# aux.net
KiCad netlist of a schematic drawn in EAGLE
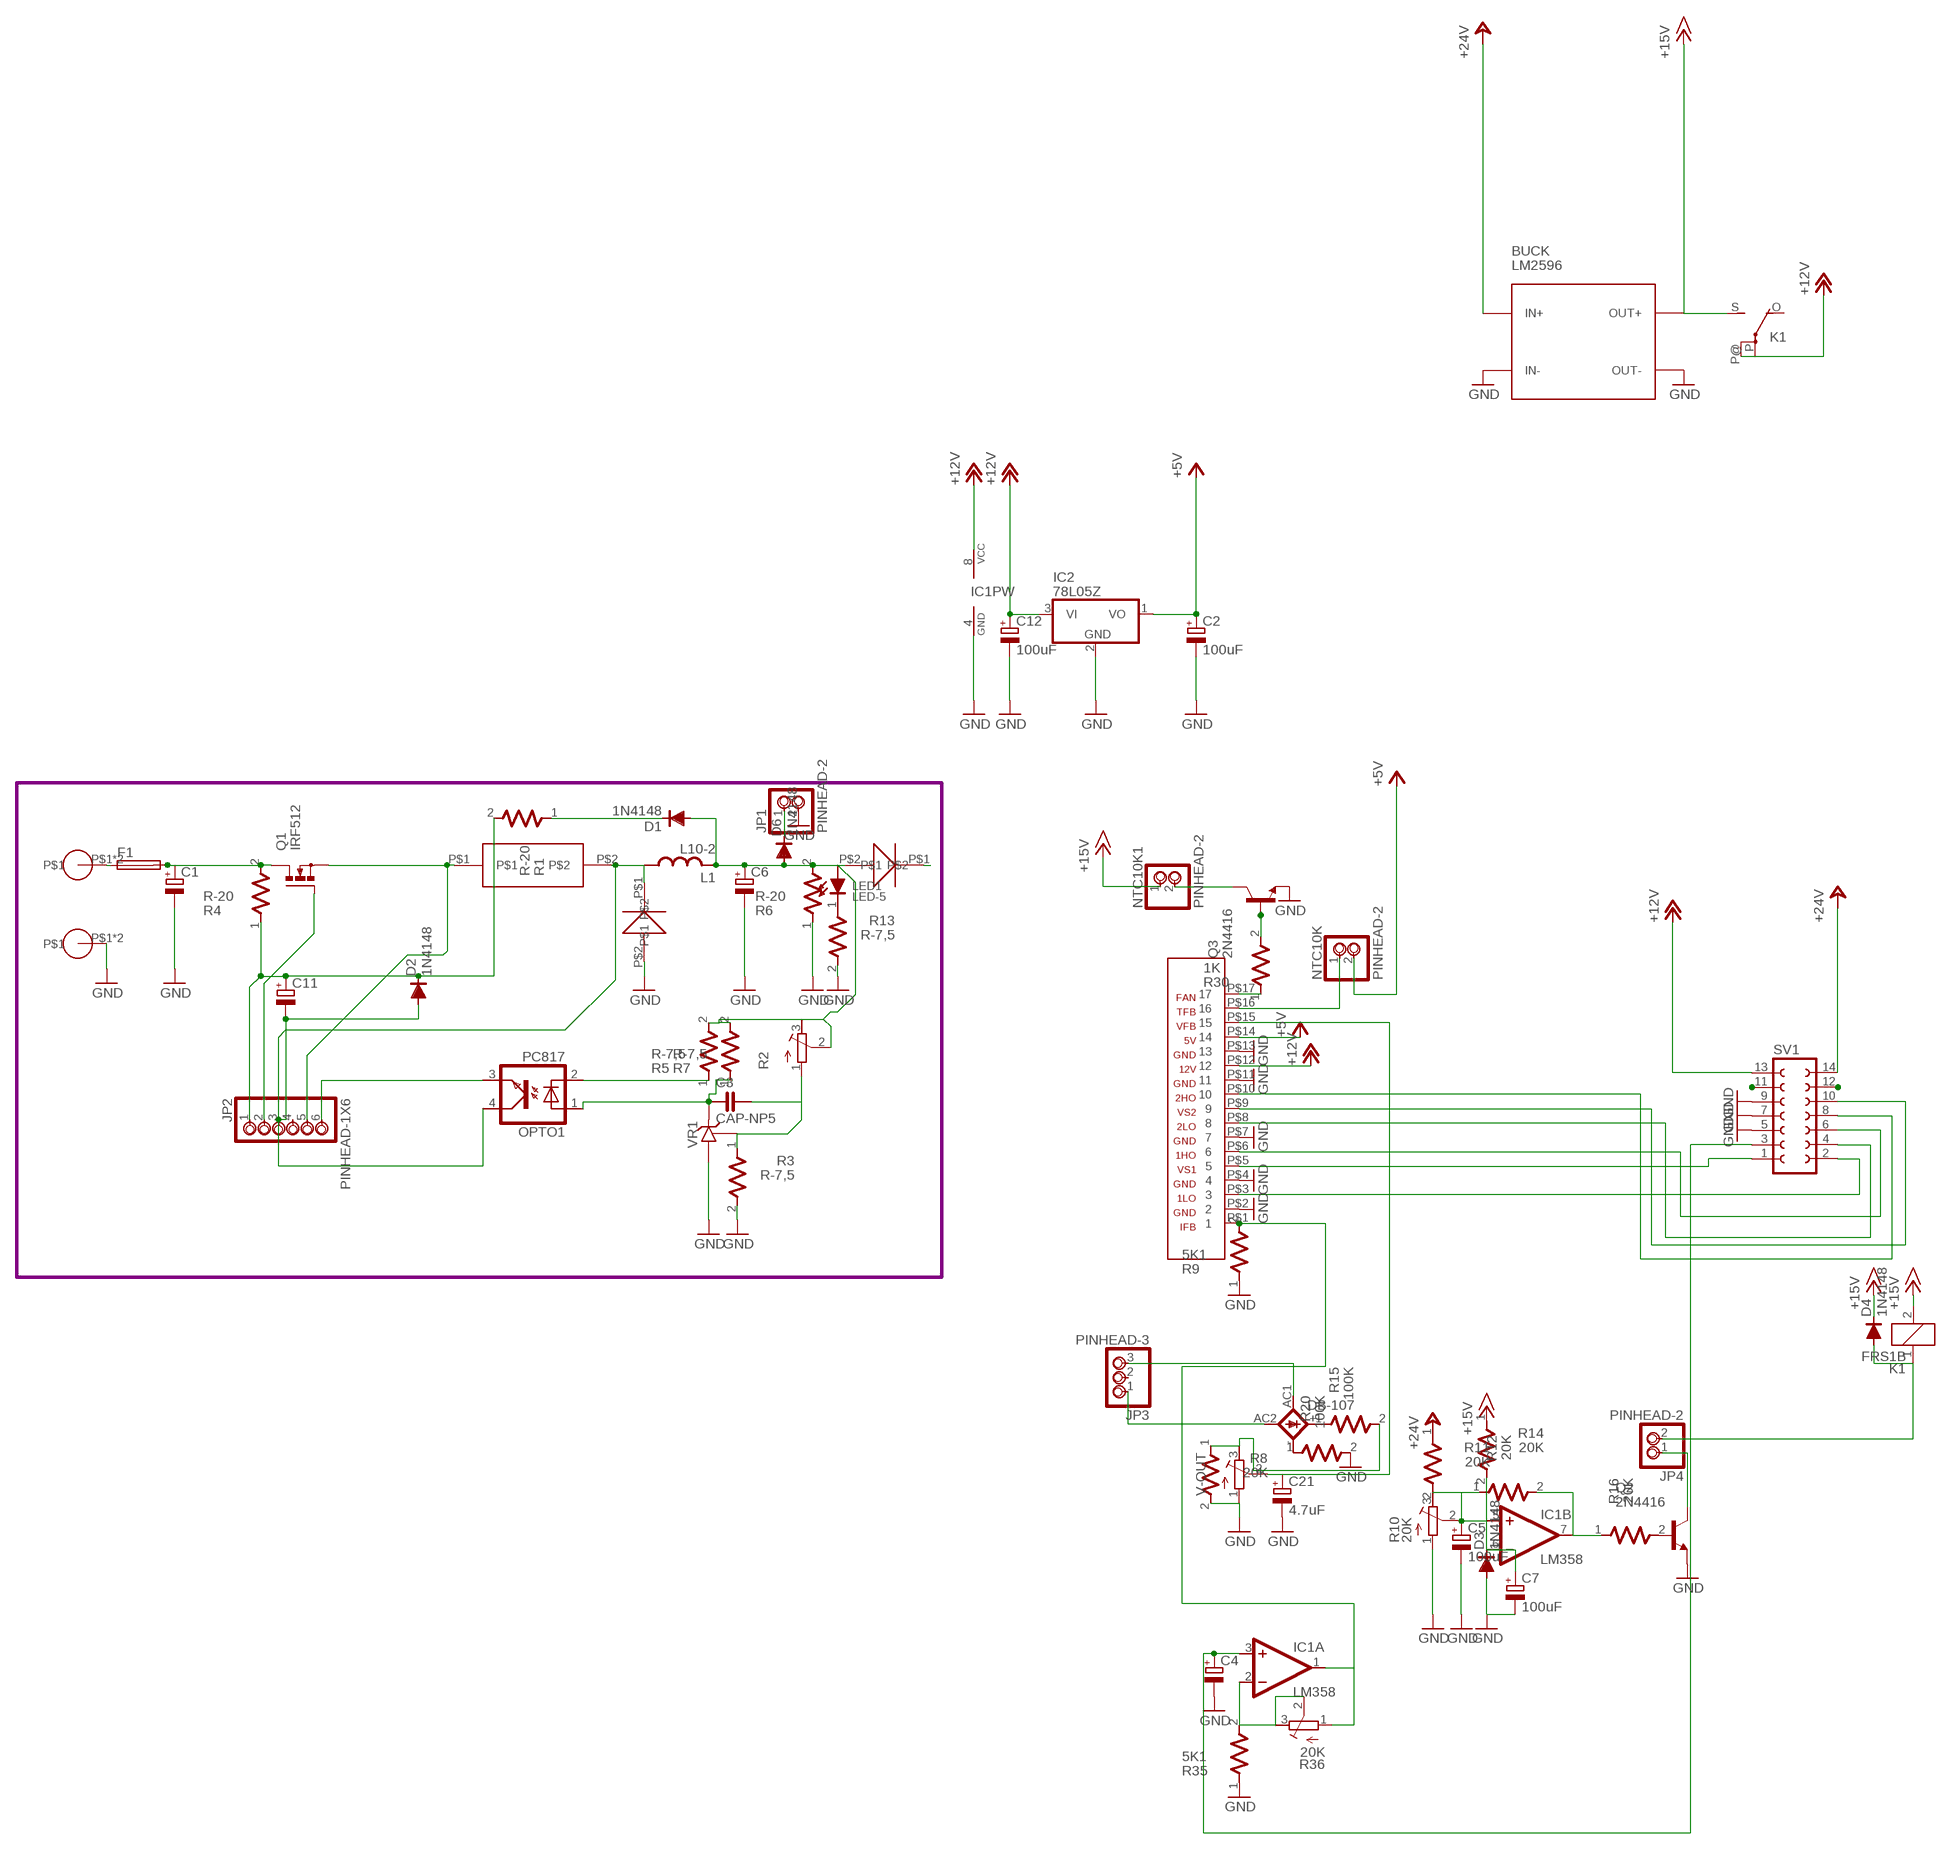
[diagram p0: schematic, sheet 1]

(export (version "E")
  (design (tool "Eeschema 10.0.6"))
  (components
    (comp (ref "BUCK")
      (value "LM2596")
      (footprint "eagle-import:DC-DC-STEP-DOWN-LM2596")
      (libsource (lib "eagle-import") (part "DC-DC-STEP-DOWN-LM2596"))
    )
    (comp (ref "C1")
      (value "CPOL-EUE7.5-18")
      (footprint "eagle-import:E7,5-18")
      (libsource (lib "eagle-import") (part "CPOL-EUE7.5-18"))
    )
    (comp (ref "C2")
      (value "100uF")
      (footprint "eagle-import:E2,5-7")
      (libsource (lib "eagle-import") (part "CPOL-EUE2.5-7"))
    )
    (comp (ref "C3")
      (value "CAP-NP5")
      (footprint "eagle-import:CAP-NP5")
      (libsource (lib "eagle-import") (part "CAP-NP5"))
    )
    (comp (ref "C4")
      (value "CPOL-EUE2.5-7")
      (footprint "eagle-import:E2,5-7")
      (libsource (lib "eagle-import") (part "CPOL-EUE2.5-7"))
    )
    (comp (ref "C5")
      (value "100uF")
      (footprint "eagle-import:E2,5-7")
      (libsource (lib "eagle-import") (part "CPOL-EUE2.5-7"))
    )
    (comp (ref "C6")
      (value "CPOL-EUE7.5-18")
      (footprint "eagle-import:E7,5-18")
      (libsource (lib "eagle-import") (part "CPOL-EUE7.5-18"))
    )
    (comp (ref "C7")
      (value "100uF")
      (footprint "eagle-import:E2,5-7")
      (libsource (lib "eagle-import") (part "CPOL-EUE2.5-7"))
    )
    (comp (ref "C11")
      (value "CPOL-EUE5-8.5")
      (footprint "eagle-import:E5-8,5")
      (libsource (lib "eagle-import") (part "CPOL-EUE5-8.5"))
    )
    (comp (ref "C12")
      (value "100uF")
      (footprint "eagle-import:E2,5-7")
      (libsource (lib "eagle-import") (part "CPOL-EUE2.5-7"))
    )
    (comp (ref "C21")
      (value "4.7uF")
      (footprint "eagle-import:E2,5-7")
      (libsource (lib "eagle-import") (part "CPOL-EUE2.5-7"))
    )
    (comp (ref "D1")
      (value "1N4148")
      (footprint "eagle-import:D-7,5")
      (libsource (lib "eagle-import") (part "1N4148"))
    )
    (comp (ref "D2")
      (value "1N4148")
      (footprint "eagle-import:D-7,5")
      (libsource (lib "eagle-import") (part "1N4148"))
    )
    (comp (ref "D3")
      (value "1N4148")
      (footprint "eagle-import:D-7,5")
      (libsource (lib "eagle-import") (part "1N4148"))
    )
    (comp (ref "D4")
      (value "1N4148")
      (footprint "eagle-import:D-7,5")
      (libsource (lib "eagle-import") (part "1N4148"))
    )
    (comp (ref "D6")
      (value "1N4148")
      (footprint "eagle-import:D-7,5")
      (libsource (lib "eagle-import") (part "1N4148"))
    )
    (comp (ref "DB-107")
      (value "CAU-1A")
      (footprint "eagle-import:CAU-1A")
      (libsource (lib "eagle-import") (part "CAU-1A"))
    )
    (comp (ref "F1")
      (value "SH22")
      (footprint "eagle-import:SH22")
      (libsource (lib "eagle-import") (part "SH22"))
    )
    (comp (ref "IC1")
      (value "LM358")
      (footprint "eagle-import:DIL-8")
      (libsource (lib "eagle-import") (part "LM358"))
    )
    (comp (ref "IC2")
      (value "78L05Z")
      (footprint "eagle-import:TO92")
      (libsource (lib "eagle-import") (part "78ZL05"))
    )
    (comp (ref "JP1")
      (value "PINHEAD-2")
      (footprint "eagle-import:PINHEAD-2")
      (libsource (lib "eagle-import") (part "chuong_PINHEAD-2"))
    )
    (comp (ref "JP2")
      (value "PINHEAD-1X6")
      (footprint "eagle-import:PINHEAD-1X6")
      (libsource (lib "eagle-import") (part "PINHEAD-1X6"))
    )
    (comp (ref "JP3")
      (value "PINHEAD-3")
      (footprint "eagle-import:PINHEAD-3")
      (libsource (lib "eagle-import") (part "PINHEAD-3"))
    )
    (comp (ref "JP4")
      (value "PINHEAD-2")
      (footprint "eagle-import:PINHEAD-2")
      (libsource (lib "eagle-import") (part "chuong_PINHEAD-2"))
    )
    (comp (ref "K1")
      (value "FRS1B")
      (footprint "eagle-import:FRS1B")
      (libsource (lib "eagle-import") (part "FRS1B"))
    )
    (comp (ref "L1")
      (value "L10-2")
      (footprint "eagle-import:L10-2")
      (libsource (lib "eagle-import") (part "L10-2"))
    )
    (comp (ref "LED1")
      (value "LED-5")
      (footprint "eagle-import:LED5")
      (libsource (lib "eagle-import") (part "LED-5"))
    )
    (comp (ref "NTC10K")
      (value "PINHEAD-2")
      (footprint "eagle-import:PINHEAD-2")
      (libsource (lib "eagle-import") (part "PINHEAD-2"))
    )
    (comp (ref "NTC10K1")
      (value "PINHEAD-2")
      (footprint "eagle-import:PINHEAD-2")
      (libsource (lib "eagle-import") (part "PINHEAD-2"))
    )
    (comp (ref "OPTO1")
      (value "PC817")
      (footprint "eagle-import:DIL-04")
      (libsource (lib "eagle-import") (part "PC817"))
    )
    (comp (ref "Q1")
      (value "IRF512")
      (footprint "eagle-import:TO220BV")
      (libsource (lib "eagle-import") (part "IRF512"))
    )
    (comp (ref "Q2")
      (value "2N4416")
      (footprint "eagle-import:TO92")
      (libsource (lib "eagle-import") (part "2N4416"))
    )
    (comp (ref "Q3")
      (value "2N4416")
      (footprint "eagle-import:TO92")
      (libsource (lib "eagle-import") (part "2N4416"))
    )
    (comp (ref "R1")
      (value "R-20")
      (footprint "eagle-import:R-20")
      (libsource (lib "eagle-import") (part "R-20"))
    )
    (comp (ref "R2")
      (value "R-TRIMM64W")
      (footprint "eagle-import:RTRIM64W")
      (libsource (lib "eagle-import") (part "R-TRIMM64W"))
    )
    (comp (ref "R3")
      (value "R-7,5")
      (footprint "eagle-import:R-7,5")
      (libsource (lib "eagle-import") (part "R-7,5"))
    )
    (comp (ref "R4")
      (value "R-20")
      (footprint "eagle-import:R-20")
      (libsource (lib "eagle-import") (part "R-20"))
    )
    (comp (ref "R5")
      (value "R-7,5")
      (footprint "eagle-import:R-7,5")
      (libsource (lib "eagle-import") (part "R-7,5"))
    )
    (comp (ref "R6")
      (value "R-20")
      (footprint "eagle-import:R-20")
      (libsource (lib "eagle-import") (part "R-20"))
    )
    (comp (ref "R7")
      (value "R-7,5")
      (footprint "eagle-import:R-7,5")
      (libsource (lib "eagle-import") (part "R-7,5"))
    )
    (comp (ref "R8")
      (value "20K")
      (footprint "eagle-import:R-7,5")
      (libsource (lib "eagle-import") (part "R-7,5"))
    )
    (comp (ref "R9")
      (value "5K1")
      (footprint "eagle-import:R-7,5")
      (libsource (lib "eagle-import") (part "R-7,5"))
    )
    (comp (ref "R10")
      (value "20K")
      (footprint "eagle-import:RTRIM64W")
      (libsource (lib "eagle-import") (part "R-TRIMM64W"))
    )
    (comp (ref "R11")
      (value "20K")
      (footprint "eagle-import:R-7,5")
      (libsource (lib "eagle-import") (part "R-7,5"))
    )
    (comp (ref "R12")
      (value "20K")
      (footprint "eagle-import:R-7,5")
      (libsource (lib "eagle-import") (part "R-7,5"))
    )
    (comp (ref "R13")
      (value "R-7,5")
      (footprint "eagle-import:R-7,5")
      (libsource (lib "eagle-import") (part "R-7,5"))
    )
    (comp (ref "R14")
      (value "20K")
      (footprint "eagle-import:R-7,5")
      (libsource (lib "eagle-import") (part "R-7,5"))
    )
    (comp (ref "R15")
      (value "100K")
      (footprint "eagle-import:R-7,5")
      (libsource (lib "eagle-import") (part "R-7,5"))
    )
    (comp (ref "R16")
      (value "20K")
      (footprint "eagle-import:R-7,5")
      (libsource (lib "eagle-import") (part "R-7,5"))
    )
    (comp (ref "R20")
      (value "100K")
      (footprint "eagle-import:R-7,5")
      (libsource (lib "eagle-import") (part "R-7,5"))
    )
    (comp (ref "R30")
      (value "1K")
      (footprint "eagle-import:R-7,5")
      (libsource (lib "eagle-import") (part "R-7,5"))
    )
    (comp (ref "R35")
      (value "5K1")
      (footprint "eagle-import:R-7,5")
      (libsource (lib "eagle-import") (part "R-7,5"))
    )
    (comp (ref "R36")
      (value "20K")
      (footprint "eagle-import:RTRIM64W")
      (libsource (lib "eagle-import") (part "R-TRIMM64W"))
    )
    (comp (ref "SV1")
      (value "FE07-2")
      (footprint "eagle-import:FE07-2")
      (libsource (lib "eagle-import") (part "FE07-2"))
    )
    (comp (ref "U$1")
      (value "DSEI6060A")
      (footprint "eagle-import:DSEI6060A")
      (libsource (lib "eagle-import") (part "DSEI6060A"))
    )
    (comp (ref "U$2")
      (value "DSEI6060A")
      (footprint "eagle-import:DSEI6060A")
      (libsource (lib "eagle-import") (part "DSEI6060A"))
    )
    (comp (ref "U$3")
      (value "PIN5MM")
      (footprint "eagle-import:PIN5MM")
      (libsource (lib "eagle-import") (part "PIN5MM"))
    )
    (comp (ref "U$4")
      (value "PIN5MM")
      (footprint "eagle-import:PIN5MM")
      (libsource (lib "eagle-import") (part "PIN5MM"))
    )
    (comp (ref "U$5")
      (value "SHUNT-0.01R")
      (footprint "eagle-import:SHUNT-0.01R")
      (libsource (lib "eagle-import") (part "SHUNT-0.01R"))
    )
    (comp (ref "U$11")
      (value "EGS002")
      (footprint "eagle-import:EGS002")
      (libsource (lib "eagle-import") (part "EGS002"))
    )
    (comp (ref "V-OUT")
      (value "R-TRIMM64W")
      (footprint "eagle-import:RTRIM64W")
      (libsource (lib "eagle-import") (part "R-TRIMM64W"))
    )
    (comp (ref "VR1")
      (value "TL431CLP")
      (footprint "eagle-import:TO92-CLP")
      (libsource (lib "eagle-import") (part "TL431CLP"))
    )
  )
  (nets
    (net (code "1") (name "+5V") (class "Default")
      (node (ref "C2") (pin "+") (pinfunction "+_+") (pintype "passive"))
      (node (ref "IC2") (pin "1") (pinfunction "VO_1") (pintype "passive"))
      (node (ref "NTC10K") (pin "2") (pinfunction "2_2") (pintype "passive"))
      (node (ref "U$11") (pin "P$14") (pinfunction "14_P$14") (pintype "bidirectional"))
    )
    (net (code "2") (name "+12V") (class "Default")
      (node (ref "C12") (pin "+") (pinfunction "+_+") (pintype "passive"))
      (node (ref "IC1") (pin "8") (pinfunction "VCC_8") (pintype "power_in"))
      (node (ref "IC2") (pin "3") (pinfunction "VI_3") (pintype "input"))
      (node (ref "K1") (pin "P") (pinfunction "P_P") (pintype "passive"))
      (node (ref "K1") (pin "P@") (pinfunction "P_P@") (pintype "passive"))
      (node (ref "SV1") (pin "13") (pinfunction "13_13") (pintype "passive"))
      (node (ref "U$11") (pin "P$12") (pinfunction "12_P$12") (pintype "bidirectional"))
    )
    (net (code "3") (name "+15V") (class "Default")
      (node (ref "BUCK") (pin "OUT+") (pinfunction "OUT+_OUT+") (pintype "bidirectional"))
      (node (ref "D4") (pin "C") (pinfunction "C_C") (pintype "passive"))
      (node (ref "K1") (pin "2") (pinfunction "2_2") (pintype "passive"))
      (node (ref "K1") (pin "S") (pinfunction "S_S") (pintype "passive"))
      (node (ref "NTC10K1") (pin "1") (pinfunction "1_1") (pintype "passive"))
      (node (ref "R14") (pin "1") (pinfunction "1_1") (pintype "passive"))
    )
    (net (code "4") (name "+24V") (class "Default")
      (node (ref "BUCK") (pin "IN+") (pinfunction "IN+_IN+") (pintype "bidirectional"))
      (node (ref "R11") (pin "1") (pinfunction "1_1") (pintype "passive"))
      (node (ref "SV1") (pin "14") (pinfunction "14_14") (pintype "passive"))
    )
    (net (code "5") (name "GND") (class "Default")
      (node (ref "BUCK") (pin "IN-") (pinfunction "IN-_IN-") (pintype "bidirectional"))
      (node (ref "BUCK") (pin "OUT-") (pinfunction "OUT-_OUT-") (pintype "bidirectional"))
      (node (ref "C1") (pin "-") (pinfunction "-_-") (pintype "passive"))
      (node (ref "C12") (pin "-") (pinfunction "-_-") (pintype "passive"))
      (node (ref "C2") (pin "-") (pinfunction "-_-") (pintype "passive"))
      (node (ref "C21") (pin "-") (pinfunction "-_-") (pintype "passive"))
      (node (ref "C4") (pin "-") (pinfunction "-_-") (pintype "passive"))
      (node (ref "C5") (pin "-") (pinfunction "-_-") (pintype "passive"))
      (node (ref "C6") (pin "-") (pinfunction "-_-") (pintype "passive"))
      (node (ref "C7") (pin "-") (pinfunction "-_-") (pintype "passive"))
      (node (ref "D3") (pin "A") (pinfunction "A_A") (pintype "passive"))
      (node (ref "IC1") (pin "4") (pinfunction "GND_4") (pintype "power_in"))
      (node (ref "IC2") (pin "2") (pinfunction "GND_2") (pintype "passive"))
      (node (ref "JP1") (pin "2") (pinfunction "2_2") (pintype "passive"))
      (node (ref "Q2") (pin "3") (pinfunction "E_3") (pintype "passive"))
      (node (ref "Q3") (pin "3") (pinfunction "E_3") (pintype "passive"))
      (node (ref "R10") (pin "1") (pinfunction "A_1") (pintype "passive"))
      (node (ref "R13") (pin "2") (pinfunction "2_2") (pintype "passive"))
      (node (ref "R20") (pin "2") (pinfunction "2_2") (pintype "passive"))
      (node (ref "R3") (pin "2") (pinfunction "2_2") (pintype "passive"))
      (node (ref "R35") (pin "1") (pinfunction "1_1") (pintype "passive"))
      (node (ref "R6") (pin "1") (pinfunction "1_1") (pintype "passive"))
      (node (ref "R8") (pin "2") (pinfunction "2_2") (pintype "passive"))
      (node (ref "R9") (pin "1") (pinfunction "1_1") (pintype "passive"))
      (node (ref "SV1") (pin "5") (pinfunction "5_5") (pintype "passive"))
      (node (ref "SV1") (pin "7") (pinfunction "7_7") (pintype "passive"))
      (node (ref "SV1") (pin "9") (pinfunction "9_9") (pintype "passive"))
      (node (ref "U$1") (pin "P$2") (pinfunction "P$2_P$2") (pintype "bidirectional"))
      (node (ref "U$11") (pin "P$11") (pinfunction "11_P$11") (pintype "bidirectional"))
      (node (ref "U$11") (pin "P$13") (pinfunction "13_P$13") (pintype "bidirectional"))
      (node (ref "U$11") (pin "P$2") (pinfunction "2_P$2") (pintype "bidirectional"))
      (node (ref "U$11") (pin "P$4") (pinfunction "4_P$4") (pintype "bidirectional"))
      (node (ref "U$11") (pin "P$7") (pinfunction "7_P$7") (pintype "bidirectional"))
      (node (ref "U$3") (pin "P$1") (pinfunction "P$1_P$1") (pintype "bidirectional"))
      (node (ref "U$3") (pin "P$2") (pinfunction "P$1_P$2") (pintype "bidirectional"))
      (node (ref "V-OUT") (pin "1") (pinfunction "A_1") (pintype "passive"))
      (node (ref "VR1") (pin "A") (pinfunction "A_A") (pintype "passive"))
    )
    (net (code "6") (name "Net-(D1-PadC)") (class "Default")
      (node (ref "D1") (pin "C") (pinfunction "C_C") (pintype "passive"))
      (node (ref "R1") (pin "1") (pinfunction "1_1") (pintype "passive"))
    )
    (net (code "7") (name "Net-(D4-PadA)") (class "Default")
      (node (ref "D4") (pin "A") (pinfunction "A_A") (pintype "passive"))
      (node (ref "JP4") (pin "2") (pinfunction "2_2") (pintype "passive"))
      (node (ref "K1") (pin "1") (pinfunction "1_1") (pintype "passive"))
    )
    (net (code "8") (name "Net-(D6-PadC)") (class "Default")
      (node (ref "D6") (pin "C") (pinfunction "C_C") (pintype "passive"))
      (node (ref "JP1") (pin "1") (pinfunction "1_1") (pintype "passive"))
    )
    (net (code "9") (name "Net-(DB-107--)") (class "Default")
      (node (ref "DB-107") (pin "AC2") (pinfunction "-_AC2") (pintype "passive"))
      (node (ref "JP3") (pin "1") (pinfunction "1_1") (pintype "passive"))
    )
    (net (code "10") (name "Net-(DB-107-AC2)") (class "Default")
      (node (ref "DB-107") (pin "-") (pinfunction "AC2_-") (pintype "passive"))
      (node (ref "R20") (pin "1") (pinfunction "1_1") (pintype "passive"))
    )
    (net (code "11") (name "Net-(DB-107-Pad+)") (class "Default")
      (node (ref "DB-107") (pin "+") (pinfunction "+_+") (pintype "passive"))
      (node (ref "R15") (pin "1") (pinfunction "1_1") (pintype "passive"))
    )
    (net (code "12") (name "Net-(DB-107-PadAC1)") (class "Default")
      (node (ref "DB-107") (pin "AC1") (pinfunction "AC1_AC1") (pintype "passive"))
      (node (ref "JP3") (pin "3") (pinfunction "3_3") (pintype "passive"))
    )
    (net (code "13") (name "Net-(F1-Pad1)") (class "Default")
      (node (ref "F1") (pin "1") (pinfunction "1_1") (pintype "passive"))
      (node (ref "U$4") (pin "P$1") (pinfunction "P$1_P$1") (pintype "bidirectional"))
      (node (ref "U$4") (pin "P$2") (pinfunction "P$1_P$2") (pintype "bidirectional"))
    )
    (net (code "14") (name "Net-(IC1A-+IN)") (class "Default")
      (node (ref "C4") (pin "+") (pinfunction "+_+") (pintype "passive"))
      (node (ref "IC1") (pin "3") (pinfunction "+IN_3") (pintype "input"))
      (node (ref "SV1") (pin "3") (pinfunction "3_3") (pintype "passive"))
    )
    (net (code "15") (name "Net-(IC1A--IN)") (class "Default")
      (node (ref "IC1") (pin "2") (pinfunction "-IN_2") (pintype "input"))
      (node (ref "R35") (pin "2") (pinfunction "2_2") (pintype "passive"))
      (node (ref "R36") (pin "2") (pinfunction "S_2") (pintype "passive"))
      (node (ref "R36") (pin "3") (pinfunction "E_3") (pintype "passive"))
    )
    (net (code "16") (name "Net-(IC1A-OUT)") (class "Default")
      (node (ref "IC1") (pin "1") (pinfunction "OUT_1") (pintype "output"))
      (node (ref "R36") (pin "1") (pinfunction "A_1") (pintype "passive"))
      (node (ref "R9") (pin "2") (pinfunction "2_2") (pintype "passive"))
      (node (ref "U$11") (pin "P$1") (pinfunction "1_P$1") (pintype "bidirectional"))
    )
    (net (code "17") (name "Net-(IC1B-+IN)") (class "Default")
      (node (ref "C5") (pin "+") (pinfunction "+_+") (pintype "passive"))
      (node (ref "IC1") (pin "5") (pinfunction "+IN_5") (pintype "input"))
      (node (ref "R10") (pin "2") (pinfunction "S_2") (pintype "passive"))
      (node (ref "R10") (pin "3") (pinfunction "E_3") (pintype "passive"))
      (node (ref "R11") (pin "2") (pinfunction "2_2") (pintype "passive"))
      (node (ref "R12") (pin "1") (pinfunction "1_1") (pintype "passive"))
    )
    (net (code "18") (name "Net-(IC1B--IN)") (class "Default")
      (node (ref "C7") (pin "+") (pinfunction "+_+") (pintype "passive"))
      (node (ref "D3") (pin "C") (pinfunction "C_C") (pintype "passive"))
      (node (ref "IC1") (pin "6") (pinfunction "-IN_6") (pintype "input"))
      (node (ref "R14") (pin "2") (pinfunction "2_2") (pintype "passive"))
    )
    (net (code "19") (name "Net-(IC1B-OUT)") (class "Default")
      (node (ref "IC1") (pin "7") (pinfunction "OUT_7") (pintype "output"))
      (node (ref "R12") (pin "2") (pinfunction "2_2") (pintype "passive"))
      (node (ref "R16") (pin "1") (pinfunction "1_1") (pintype "passive"))
    )
    (net (code "20") (name "Net-(JP2-Pad2)") (class "Default")
      (node (ref "JP2") (pin "2") (pinfunction "2_2") (pintype "passive"))
      (node (ref "Q1") (pin "G") (pinfunction "G_G") (pintype "passive"))
    )
    (net (code "21") (name "Net-(JP2-Pad5)") (class "Default")
      (node (ref "JP2") (pin "5") (pinfunction "5_5") (pintype "passive"))
      (node (ref "Q1") (pin "S") (pinfunction "S_S") (pintype "passive"))
      (node (ref "U$5") (pin "P$1") (pinfunction "P$1_P$1") (pintype "bidirectional"))
    )
    (net (code "22") (name "Net-(LED1-PadK)") (class "Default")
      (node (ref "LED1") (pin "K") (pinfunction "K_K") (pintype "passive"))
      (node (ref "R13") (pin "1") (pinfunction "1_1") (pintype "passive"))
    )
    (net (code "23") (name "Net-(OPTO1-A)") (class "Default")
      (node (ref "C3") (pin "1") (pinfunction "1_1") (pintype "passive"))
      (node (ref "OPTO1") (pin "1") (pinfunction "A_1") (pintype "passive"))
      (node (ref "R7") (pin "1") (pinfunction "1_1") (pintype "passive"))
      (node (ref "VR1") (pin "C") (pinfunction "C_C") (pintype "passive"))
    )
    (net (code "24") (name "Net-(OPTO1-C)") (class "Default")
      (node (ref "OPTO1") (pin "2") (pinfunction "C_2") (pintype "passive"))
      (node (ref "R5") (pin "1") (pinfunction "1_1") (pintype "passive"))
    )
    (net (code "25") (name "Net-(OPTO1-COL)") (class "Default")
      (node (ref "C11") (pin "-") (pinfunction "-_-") (pintype "passive"))
      (node (ref "D2") (pin "A") (pinfunction "A_A") (pintype "passive"))
      (node (ref "JP2") (pin "3") (pinfunction "3_3") (pintype "passive"))
      (node (ref "L1") (pin "P$1") (pinfunction "1_P$1") (pintype "passive"))
      (node (ref "L1") (pin "P$2") (pinfunction "1_P$2") (pintype "passive"))
      (node (ref "OPTO1") (pin "4") (pinfunction "COL_4") (pintype "passive"))
      (node (ref "U$1") (pin "P$1") (pinfunction "P$1_P$1") (pintype "bidirectional"))
      (node (ref "U$5") (pin "P$2") (pinfunction "P$2_P$2") (pintype "bidirectional"))
    )
    (net (code "26") (name "Net-(OPTO1-EMI)") (class "Default")
      (node (ref "JP2") (pin "6") (pinfunction "6_6") (pintype "passive"))
      (node (ref "OPTO1") (pin "3") (pinfunction "EMI_3") (pintype "passive"))
    )
    (net (code "27") (name "Net-(Q2-B)") (class "Default")
      (node (ref "Q2") (pin "2") (pinfunction "B_2") (pintype "passive"))
      (node (ref "R16") (pin "2") (pinfunction "2_2") (pintype "passive"))
    )
    (net (code "28") (name "Net-(Q2-C)") (class "Default")
      (node (ref "JP4") (pin "1") (pinfunction "1_1") (pintype "passive"))
      (node (ref "Q2") (pin "1") (pinfunction "C_1") (pintype "passive"))
    )
    (net (code "29") (name "Net-(Q3-B)") (class "Default")
      (node (ref "Q3") (pin "2") (pinfunction "B_2") (pintype "passive"))
      (node (ref "R30") (pin "2") (pinfunction "2_2") (pintype "passive"))
    )
    (net (code "30") (name "Net-(Q3-C)") (class "Default")
      (node (ref "NTC10K1") (pin "2") (pinfunction "2_2") (pintype "passive"))
      (node (ref "Q3") (pin "1") (pinfunction "C_1") (pintype "passive"))
    )
    (net (code "31") (name "Net-(R1-3)") (class "Default")
      (node (ref "C11") (pin "+") (pinfunction "+_+") (pintype "passive"))
      (node (ref "D2") (pin "C") (pinfunction "C_C") (pintype "passive"))
      (node (ref "JP2") (pin "1") (pinfunction "1_1") (pintype "passive"))
      (node (ref "R1") (pin "2") (pinfunction "3_2") (pintype "passive"))
      (node (ref "R4") (pin "1") (pinfunction "1_1") (pintype "passive"))
    )
    (net (code "32") (name "Net-(R2-A)") (class "Default")
      (node (ref "C3") (pin "2") (pinfunction "2_2") (pintype "passive"))
      (node (ref "R2") (pin "1") (pinfunction "A_1") (pintype "passive"))
      (node (ref "R3") (pin "1") (pinfunction "1_1") (pintype "passive"))
      (node (ref "VR1") (pin "R") (pinfunction "R_R") (pintype "passive"))
    )
    (net (code "33") (name "Net-(R2-E)") (class "Default")
      (node (ref "C6") (pin "+") (pinfunction "+_+") (pintype "passive"))
      (node (ref "D1") (pin "A") (pinfunction "A_A") (pintype "passive"))
      (node (ref "D6") (pin "A") (pinfunction "A_A") (pintype "passive"))
      (node (ref "L1") (pin "P$3") (pinfunction "2_P$3") (pintype "passive"))
      (node (ref "L1") (pin "P$4") (pinfunction "2_P$4") (pintype "passive"))
      (node (ref "LED1") (pin "A") (pinfunction "A_A") (pintype "passive"))
      (node (ref "R2") (pin "2") (pinfunction "S_2") (pintype "passive"))
      (node (ref "R2") (pin "3") (pinfunction "E_3") (pintype "passive"))
      (node (ref "R5") (pin "2") (pinfunction "2_2") (pintype "passive"))
      (node (ref "R6") (pin "2") (pinfunction "3_2") (pintype "passive"))
      (node (ref "R7") (pin "2") (pinfunction "2_2") (pintype "passive"))
      (node (ref "U$2") (pin "P$2") (pinfunction "P$2_P$2") (pintype "bidirectional"))
    )
    (net (code "34") (name "Net-(R4-3)") (class "Default")
      (node (ref "C1") (pin "+") (pinfunction "+_+") (pintype "passive"))
      (node (ref "F1") (pin "2") (pinfunction "2_2") (pintype "passive"))
      (node (ref "Q1") (pin "D") (pinfunction "D_D") (pintype "passive"))
      (node (ref "R4") (pin "2") (pinfunction "3_2") (pintype "passive"))
    )
    (net (code "35") (name "Net-(U$11-3)") (class "Default")
      (node (ref "SV1") (pin "2") (pinfunction "2_2") (pintype "passive"))
      (node (ref "U$11") (pin "P$3") (pinfunction "3_P$3") (pintype "bidirectional"))
    )
    (net (code "36") (name "Net-(U$11-5)") (class "Default")
      (node (ref "SV1") (pin "1") (pinfunction "1_1") (pintype "passive"))
      (node (ref "U$11") (pin "P$5") (pinfunction "5_P$5") (pintype "bidirectional"))
    )
    (net (code "37") (name "Net-(U$11-6)") (class "Default")
      (node (ref "SV1") (pin "6") (pinfunction "6_6") (pintype "passive"))
      (node (ref "U$11") (pin "P$6") (pinfunction "6_P$6") (pintype "bidirectional"))
    )
    (net (code "38") (name "Net-(U$11-8)") (class "Default")
      (node (ref "SV1") (pin "4") (pinfunction "4_4") (pintype "passive"))
      (node (ref "U$11") (pin "P$8") (pinfunction "8_P$8") (pintype "bidirectional"))
    )
    (net (code "39") (name "Net-(U$11-9)") (class "Default")
      (node (ref "SV1") (pin "10") (pinfunction "10_10") (pintype "passive"))
      (node (ref "U$11") (pin "P$9") (pinfunction "9_P$9") (pintype "bidirectional"))
    )
    (net (code "40") (name "Net-(U$11-10)") (class "Default")
      (node (ref "SV1") (pin "8") (pinfunction "8_8") (pintype "passive"))
      (node (ref "U$11") (pin "P$10") (pinfunction "10_P$10") (pintype "bidirectional"))
    )
    (net (code "41") (name "Net-(U$11-15)") (class "Default")
      (node (ref "C21") (pin "+") (pinfunction "+_+") (pintype "passive"))
      (node (ref "U$11") (pin "P$15") (pinfunction "15_P$15") (pintype "bidirectional"))
      (node (ref "V-OUT") (pin "2") (pinfunction "S_2") (pintype "passive"))
    )
    (net (code "42") (name "Net-(U$11-16)") (class "Default")
      (node (ref "NTC10K") (pin "1") (pinfunction "1_1") (pintype "passive"))
      (node (ref "U$11") (pin "P$16") (pinfunction "16_P$16") (pintype "bidirectional"))
    )
    (net (code "43") (name "Net-(U$11-17)") (class "Default")
      (node (ref "R30") (pin "1") (pinfunction "1_1") (pintype "passive"))
      (node (ref "U$11") (pin "P$17") (pinfunction "17_P$17") (pintype "bidirectional"))
    )
    (net (code "44") (name "Net-(V-OUT-E)") (class "Default")
      (node (ref "R15") (pin "2") (pinfunction "2_2") (pintype "passive"))
      (node (ref "R8") (pin "1") (pinfunction "1_1") (pintype "passive"))
      (node (ref "V-OUT") (pin "3") (pinfunction "E_3") (pintype "passive"))
    )
    (net (code "45") (name "unconnected-(JP2-Pad4)") (class "Default")
      (node (ref "JP2") (pin "4") (pinfunction "4_4") (pintype "passive"))
    )
    (net (code "46") (name "unconnected-(JP3-Pad2)") (class "Default")
      (node (ref "JP3") (pin "2") (pinfunction "2_2") (pintype "passive"))
    )
    (net (code "47") (name "unconnected-(K1-PadO)") (class "Default")
      (node (ref "K1") (pin "O") (pinfunction "O_O") (pintype "passive"))
    )
    (net (code "48") (name "unconnected-(SV1-Pad11)") (class "Default")
      (node (ref "SV1") (pin "11") (pinfunction "11_11") (pintype "passive"))
    )
    (net (code "49") (name "unconnected-(SV1-Pad12)") (class "Default")
      (node (ref "SV1") (pin "12") (pinfunction "12_12") (pintype "passive"))
    )
    (net (code "50") (name "unconnected-(U$2-PadP$1)") (class "Default")
      (node (ref "U$2") (pin "P$1") (pinfunction "P$1_P$1") (pintype "bidirectional"))
    )
  )
)
